# Power.net
KiCad netlist of a schematic drawn in Altium Designer
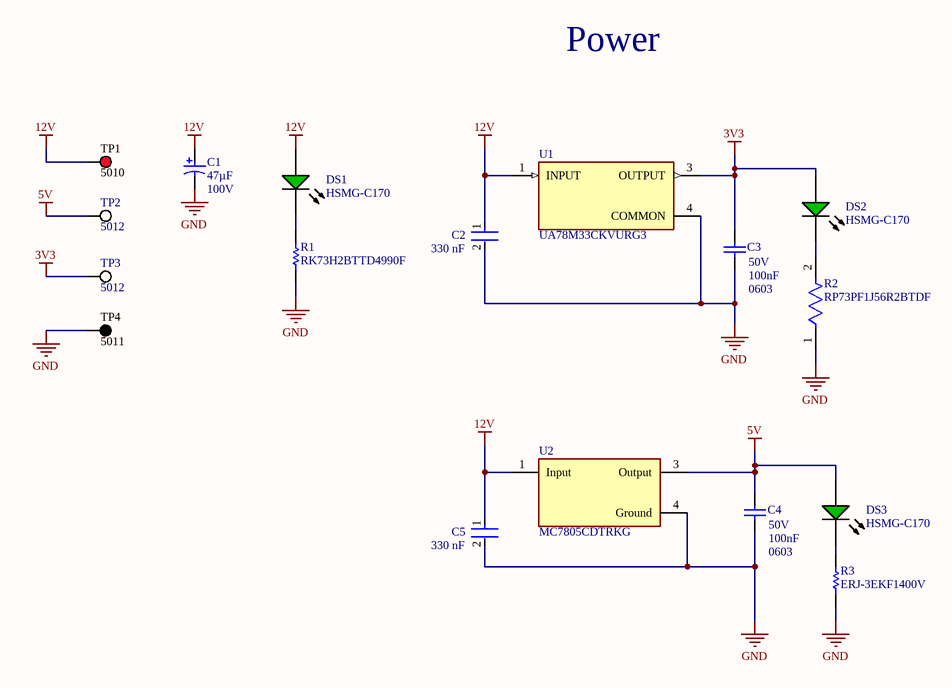
[diagram p0: Power.SchDoc]

(export (version "E")
  (design (tool "Eeschema 10.0.6"))
  (components
    (comp (ref "C1")
      (value "UUX2A470MNL1GS")
      (footprint "NIC-UUX2A470MNL1GS_L")
      (fields
        (field (name "MANUFACTURER") "Nichicon")
        (field (name "CAPACITANCE") "47µF")
        (field (name "TOLERANCE") "20%")
        (field (name "VOLTAGE") "100V")
      )
      (libsource (lib "Altium Content Vault") (part "CAP-P-2"))
    )
    (comp (ref "C2")
      (value "330 nF")
      (footprint "FP-CC0805-0_85-MFG")
      (description "Surface Mount Ceramic Multilayer Capacitor 0.33uF 10% X7R 16V 0805 Blister T/R")
      (fields (field (name "MANUFACTURER PART NUMBER") "CC0805KKX7R7BB334") (field (name "TOLERANCE") "0.1"))
      (libsource (lib "Altium Content Vault") (part "11868f565c42a9108669ba33697ecf6"))
    )
    (comp (ref "C3")
      (value "C0603X104K5RACTU")
      (footprint "CAPC1608X87X35NL15T15")
      (fields
        (field (name "MANUFACTURER") "Kemet")
        (field (name "CASE CODE (IMPERIAL)") "0603")
        (field (name "CAPACITANCE") "100nF")
        (field (name "TOLERANCE") "10%")
        (field (name "VOLTAGE") "50V")
      )
      (libsource (lib "Altium Content Vault") (part "CAP"))
    )
    (comp (ref "C4")
      (value "C0603X104K5RACTU")
      (footprint "CAPC1608X87X35NL15T15")
      (fields
        (field (name "MANUFACTURER") "Kemet")
        (field (name "CASE CODE (IMPERIAL)") "0603")
        (field (name "CAPACITANCE") "100nF")
        (field (name "TOLERANCE") "10%")
        (field (name "VOLTAGE") "50V")
      )
      (libsource (lib "Altium Content Vault") (part "CAP"))
    )
    (comp (ref "C5")
      (value "330 nF")
      (footprint "FP-CC0805-0_85-MFG")
      (description "Surface Mount Ceramic Multilayer Capacitor 0.33uF 10% X7R 16V 0805 Blister T/R")
      (fields (field (name "MANUFACTURER PART NUMBER") "CC0805KKX7R7BB334") (field (name "TOLERANCE") "0.1"))
      (libsource (lib "Altium Content Vault") (part "11868f565c42a9108669ba33697ecf6"))
    )
    (comp (ref "DS1")
      (value "HSMG-C170")
      (footprint "AVAG-HSMX-C170_V")
      (description "Chip LED, Green, 2.2 V, -40 to 85 degC, 2-Pin SMD, Pb-Free, Tape and Reel")
      (fields (field (name "MANUFACTURER") "Avago"))
      (libsource (lib "Altium Content Vault") (part "LED_GREEN_A1K2-2"))
    )
    (comp (ref "DS2")
      (value "HSMG-C170")
      (footprint "AVAG-HSMX-C170_V")
      (description "Chip LED, Green, 2.2 V, -40 to 85 degC, 2-Pin SMD, Pb-Free, Tape and Reel")
      (fields (field (name "MANUFACTURER") "Avago"))
      (libsource (lib "Altium Content Vault") (part "LED_GREEN_A1K2-2"))
    )
    (comp (ref "DS3")
      (value "HSMG-C170")
      (footprint "AVAG-HSMX-C170_V")
      (description "Chip LED, Green, 2.2 V, -40 to 85 degC, 2-Pin SMD, Pb-Free, Tape and Reel")
      (fields (field (name "MANUFACTURER") "Avago"))
      (libsource (lib "Altium Content Vault") (part "LED_GREEN_A1K2-2"))
    )
    (comp (ref "R1")
      (value "RK73H2BTTD4990F")
      (footprint "RESC3216X70X40NL20T20")
      (fields (field (name "MANUFACTURER") "KOA Speer"))
      (libsource (lib "Altium Content Vault") (part "RES"))
    )
    (comp (ref "R2")
      (value "RP73PF1J56R2BTDF")
      (footprint "FP-RP73P-1J-MFG")
      (description "RES SMD 56.2 OHM 0.1% 1/6W 0603")
      (fields
        (field (name "OCTOPART") "https://octopart.com/rp73pf1j56r2btdf-te+connectivity-45466141")
        (field (name "TOLERANCE") "0.001")
      )
      (libsource (lib "Altium Content Vault") (part "1029c3af85768c4190bb7ad29bc67b5"))
    )
    (comp (ref "R3")
      (value "ERJ-3EKF1400V")
      (footprint "RESC1608X55X30NL15T15")
      (fields (field (name "MANUFACTURER") "Panasonic"))
      (libsource (lib "Altium Content Vault") (part "RES"))
    )
    (comp (ref "TP1")
      (value "5010")
      (footprint "KSTN-5010_V")
      (description "Test Point, Red, Through Hole, RoHS, Bulk")
      (fields (field (name "MANUFACTURER") "Keystone"))
      (libsource (lib "Altium Content Vault") (part "TESTPOINT_RED"))
    )
    (comp (ref "TP2")
      (value "5012")
      (footprint "KSTN-5012_V")
      (description "Test Point, White, Through Hole, RoHS, Bulk")
      (fields (field (name "MANUFACTURER") "Keystone"))
      (libsource (lib "Altium Content Vault") (part "TESTPOINT_WHITE"))
    )
    (comp (ref "TP3")
      (value "5012")
      (footprint "KSTN-5012_V")
      (description "Test Point, White, Through Hole, RoHS, Bulk")
      (fields (field (name "MANUFACTURER") "Keystone"))
      (libsource (lib "Altium Content Vault") (part "TESTPOINT_WHITE"))
    )
    (comp (ref "TP4")
      (value "5011")
      (footprint "KSTN-5011_V")
      (description "Test Point, Black, Through Hole, RoHS, Bulk")
      (fields (field (name "MANUFACTURER") "Keystone"))
      (libsource (lib "Altium Content Vault") (part "TESTPOINT_BLACK"))
    )
    (comp (ref "U1")
      (value "UA78M33CKVURG3")
      (footprint "FP-KVU0003A-MFG")
      (description "IC REG LINEAR 3.3V 500MA TO252-3")
      (fields
        (field (name "OCTOPART") "https://octopart.com/ua78m33ckvurg3-texas+instruments-669262")
        (field (name "MANUFACTURER") "Texas Instruments")
      )
      (libsource (lib "Altium Content Vault") (part "dd3c83ac2e246cf9e0dcbcc19b382eb"))
    )
    (comp (ref "U2")
      (value "MC7805CDTRKG")
      (footprint "FP-369C-MFG")
      (description "IC REG LINEAR 5V 1A DPAK")
      (libsource (lib "Altium Content Vault") (part "10ca12a7ef27ecffb14ba267b90e28b"))
    )
  )
  (nets
    (net (code "1") (name "3V3") (class "Default")
      (node (ref "C3") (pin "2") (pinfunction "2_2") (pintype "passive"))
      (node (ref "DS2") (pin "1") (pinfunction "A_1") (pintype "passive"))
      (node (ref "TP3") (pin "1") (pinfunction "1_1") (pintype "passive"))
      (node (ref "U1") (pin "3") (pinfunction "OUTPUT_3") (pintype "output"))
    )
    (net (code "2") (name "5V") (class "Default")
      (node (ref "C4") (pin "2") (pinfunction "2_2") (pintype "passive"))
      (node (ref "DS3") (pin "1") (pinfunction "A_1") (pintype "passive"))
      (node (ref "TP2") (pin "1") (pinfunction "1_1") (pintype "passive"))
      (node (ref "U2") (pin "3") (pinfunction "Output_3") (pintype "power_in"))
    )
    (net (code "3") (name "12V") (class "Default")
      (node (ref "C1") (pin "1") (pinfunction "1_1") (pintype "passive"))
      (node (ref "C2") (pin "1") (pinfunction "1_1") (pintype "passive"))
      (node (ref "C5") (pin "1") (pinfunction "1_1") (pintype "passive"))
      (node (ref "DS1") (pin "1") (pinfunction "A_1") (pintype "passive"))
      (node (ref "TP1") (pin "1") (pinfunction "1_1") (pintype "passive"))
      (node (ref "U1") (pin "1") (pinfunction "INPUT_1") (pintype "input"))
      (node (ref "U2") (pin "1") (pinfunction "Input_1") (pintype "power_in"))
    )
    (net (code "4") (name "GND") (class "Default")
      (node (ref "C1") (pin "2") (pinfunction "2_2") (pintype "passive"))
      (node (ref "C2") (pin "2") (pinfunction "2_2") (pintype "passive"))
      (node (ref "C3") (pin "1") (pinfunction "1_1") (pintype "passive"))
      (node (ref "C4") (pin "1") (pinfunction "1_1") (pintype "passive"))
      (node (ref "C5") (pin "2") (pinfunction "2_2") (pintype "passive"))
      (node (ref "R1") (pin "1") (pinfunction "1_1") (pintype "passive"))
      (node (ref "R2") (pin "1") (pinfunction "1_1") (pintype "passive"))
      (node (ref "R3") (pin "1") (pinfunction "1_1") (pintype "passive"))
      (node (ref "TP4") (pin "1") (pinfunction "1_1") (pintype "passive"))
      (node (ref "U1") (pin "4") (pinfunction "COMMON_4") (pintype "passive"))
      (node (ref "U2") (pin "4") (pinfunction "Ground_4") (pintype "power_in"))
    )
    (net (code "5") (name "Net-(DS1-K)") (class "Default")
      (node (ref "DS1") (pin "2") (pinfunction "K_2") (pintype "passive"))
      (node (ref "R1") (pin "2") (pinfunction "2_2") (pintype "passive"))
    )
    (net (code "6") (name "Net-(DS2-K)") (class "Default")
      (node (ref "DS2") (pin "2") (pinfunction "K_2") (pintype "passive"))
      (node (ref "R2") (pin "2") (pinfunction "2_2") (pintype "passive"))
    )
    (net (code "7") (name "Net-(DS3-K)") (class "Default")
      (node (ref "DS3") (pin "2") (pinfunction "K_2") (pintype "passive"))
      (node (ref "R3") (pin "2") (pinfunction "2_2") (pintype "passive"))
    )
  )
)
